# Schematic.net
KiCad netlist of a schematic drawn in Altium Designer
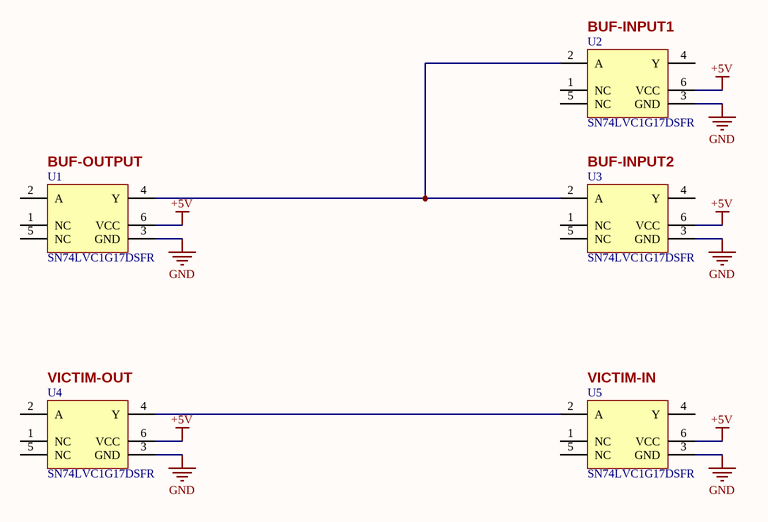
[diagram p0: Schematic.SchDoc]

(export (version "E")
  (design (tool "Eeschema 10.0.6"))
  (components
    (comp (ref "U1")
      (value "SN74LVC1G17DSFR")
      (footprint "DSF0006A_V")
      (description "Buffer, LVC/LCX/Z Series, 1-Func, 1-Input, CMOS, PDSO6")
      (fields (field (name "MANUFACTURER") "Texas Instruments"))
      (libsource (lib "Schlib") (part "SN74LVC1G17DSFR"))
    )
    (comp (ref "U2")
      (value "SN74LVC1G17DSFR")
      (footprint "DSF0006A_V")
      (description "Buffer, LVC/LCX/Z Series, 1-Func, 1-Input, CMOS, PDSO6")
      (fields (field (name "MANUFACTURER") "Texas Instruments"))
      (libsource (lib "Schlib") (part "SN74LVC1G17DSFR"))
    )
    (comp (ref "U3")
      (value "SN74LVC1G17DSFR")
      (footprint "DSF0006A_V")
      (description "Buffer, LVC/LCX/Z Series, 1-Func, 1-Input, CMOS, PDSO6")
      (fields (field (name "MANUFACTURER") "Texas Instruments"))
      (libsource (lib "Schlib") (part "SN74LVC1G17DSFR"))
    )
    (comp (ref "U4")
      (value "SN74LVC1G17DSFR")
      (footprint "DSF0006A_V")
      (description "Buffer, LVC/LCX/Z Series, 1-Func, 1-Input, CMOS, PDSO6")
      (fields (field (name "MANUFACTURER") "Texas Instruments"))
      (libsource (lib "Schlib") (part "SN74LVC1G17DSFR"))
    )
    (comp (ref "U5")
      (value "SN74LVC1G17DSFR")
      (footprint "DSF0006A_V")
      (description "Buffer, LVC/LCX/Z Series, 1-Func, 1-Input, CMOS, PDSO6")
      (fields (field (name "MANUFACTURER") "Texas Instruments"))
      (libsource (lib "Schlib") (part "SN74LVC1G17DSFR"))
    )
  )
  (nets
    (net (code "1") (name "+5V") (class "Default")
      (node (ref "U1") (pin "6") (pinfunction "VCC_6") (pintype "passive"))
      (node (ref "U2") (pin "6") (pinfunction "VCC_6") (pintype "passive"))
      (node (ref "U3") (pin "6") (pinfunction "VCC_6") (pintype "passive"))
      (node (ref "U4") (pin "6") (pinfunction "VCC_6") (pintype "passive"))
      (node (ref "U5") (pin "6") (pinfunction "VCC_6") (pintype "passive"))
    )
    (net (code "2") (name "GND") (class "Default")
      (node (ref "U1") (pin "3") (pinfunction "GND_3") (pintype "passive"))
      (node (ref "U2") (pin "3") (pinfunction "GND_3") (pintype "passive"))
      (node (ref "U3") (pin "3") (pinfunction "GND_3") (pintype "passive"))
      (node (ref "U4") (pin "3") (pinfunction "GND_3") (pintype "passive"))
      (node (ref "U5") (pin "3") (pinfunction "GND_3") (pintype "passive"))
    )
    (net (code "3") (name "Net-(U1-Y)") (class "Default")
      (node (ref "U1") (pin "4") (pinfunction "Y_4") (pintype "passive"))
      (node (ref "U2") (pin "2") (pinfunction "A_2") (pintype "passive"))
      (node (ref "U3") (pin "2") (pinfunction "A_2") (pintype "passive"))
    )
    (net (code "4") (name "Net-(U4-Y)") (class "Default")
      (node (ref "U4") (pin "4") (pinfunction "Y_4") (pintype "passive"))
      (node (ref "U5") (pin "2") (pinfunction "A_2") (pintype "passive"))
    )
    (net (code "5") (name "unconnected-(U1-A-Pad2)") (class "Default")
      (node (ref "U1") (pin "2") (pinfunction "A_2") (pintype "passive"))
    )
    (net (code "6") (name "unconnected-(U1-NC-Pad1)") (class "Default")
      (node (ref "U1") (pin "1") (pinfunction "NC_1") (pintype "passive"))
    )
    (net (code "7") (name "unconnected-(U1-NC-Pad5)") (class "Default")
      (node (ref "U1") (pin "5") (pinfunction "NC_5") (pintype "passive"))
    )
    (net (code "8") (name "unconnected-(U2-NC-Pad1)") (class "Default")
      (node (ref "U2") (pin "1") (pinfunction "NC_1") (pintype "passive"))
    )
    (net (code "9") (name "unconnected-(U2-NC-Pad5)") (class "Default")
      (node (ref "U2") (pin "5") (pinfunction "NC_5") (pintype "passive"))
    )
    (net (code "10") (name "unconnected-(U2-Y-Pad4)") (class "Default")
      (node (ref "U2") (pin "4") (pinfunction "Y_4") (pintype "passive"))
    )
    (net (code "11") (name "unconnected-(U3-NC-Pad1)") (class "Default")
      (node (ref "U3") (pin "1") (pinfunction "NC_1") (pintype "passive"))
    )
    (net (code "12") (name "unconnected-(U3-NC-Pad5)") (class "Default")
      (node (ref "U3") (pin "5") (pinfunction "NC_5") (pintype "passive"))
    )
    (net (code "13") (name "unconnected-(U3-Y-Pad4)") (class "Default")
      (node (ref "U3") (pin "4") (pinfunction "Y_4") (pintype "passive"))
    )
    (net (code "14") (name "unconnected-(U4-A-Pad2)") (class "Default")
      (node (ref "U4") (pin "2") (pinfunction "A_2") (pintype "passive"))
    )
    (net (code "15") (name "unconnected-(U4-NC-Pad1)") (class "Default")
      (node (ref "U4") (pin "1") (pinfunction "NC_1") (pintype "passive"))
    )
    (net (code "16") (name "unconnected-(U4-NC-Pad5)") (class "Default")
      (node (ref "U4") (pin "5") (pinfunction "NC_5") (pintype "passive"))
    )
    (net (code "17") (name "unconnected-(U5-NC-Pad1)") (class "Default")
      (node (ref "U5") (pin "1") (pinfunction "NC_1") (pintype "passive"))
    )
    (net (code "18") (name "unconnected-(U5-NC-Pad5)") (class "Default")
      (node (ref "U5") (pin "5") (pinfunction "NC_5") (pintype "passive"))
    )
    (net (code "19") (name "unconnected-(U5-Y-Pad4)") (class "Default")
      (node (ref "U5") (pin "4") (pinfunction "Y_4") (pintype "passive"))
    )
  )
)
